# inductor_test.net
KiCad netlist of a schematic drawn in EAGLE
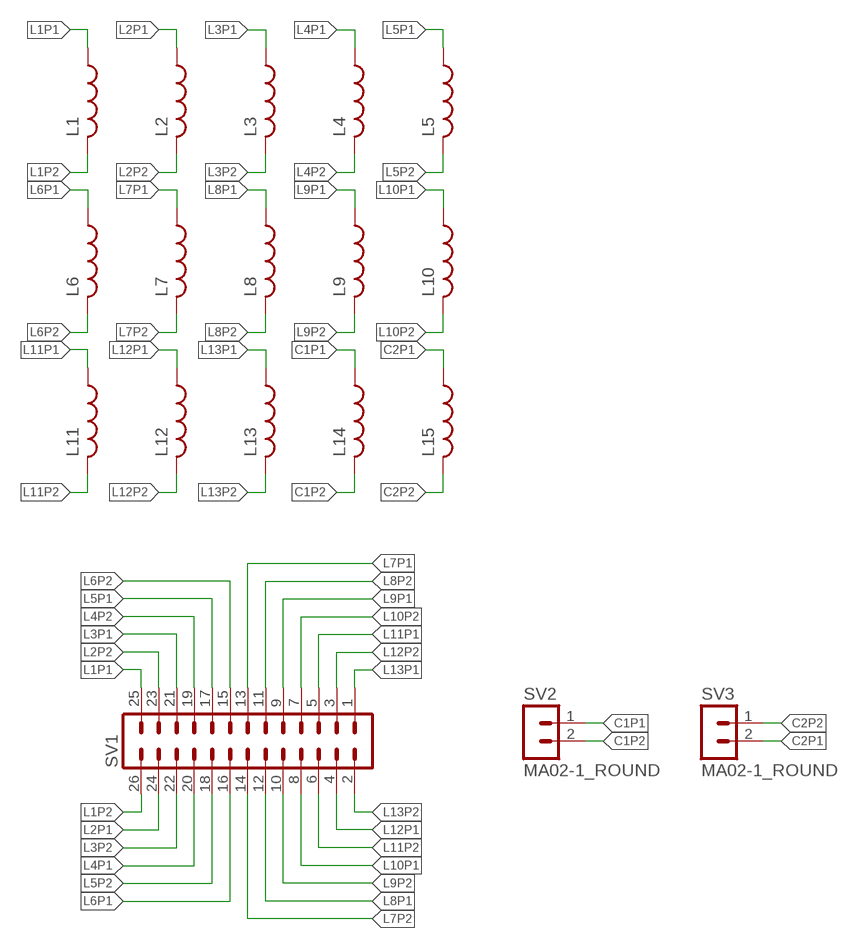
[diagram p0: schematic, sheet 1]
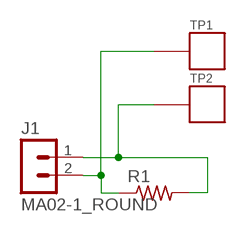
[diagram p1: schematic, sheet 2]

(export (version "E")
  (design (tool "Eeschema 10.0.6"))
  (components
    (comp (ref "L1")
      (value "L-USL0805")
      (footprint "eagle-import:L0805")
      (libsource (lib "eagle-import") (part "L-USL0805"))
    )
    (comp (ref "L2")
      (value "L-USL0805")
      (footprint "eagle-import:L0805")
      (libsource (lib "eagle-import") (part "L-USL0805"))
    )
    (comp (ref "L3")
      (value "L-USL0805")
      (footprint "eagle-import:L0805")
      (libsource (lib "eagle-import") (part "L-USL0805"))
    )
    (comp (ref "L4")
      (value "L-USL0805")
      (footprint "eagle-import:L0805")
      (libsource (lib "eagle-import") (part "L-USL0805"))
    )
    (comp (ref "L5")
      (value "L-USL0805")
      (footprint "eagle-import:L0805")
      (libsource (lib "eagle-import") (part "L-USL0805"))
    )
    (comp (ref "L6")
      (value "L-USL0805")
      (footprint "eagle-import:L0805")
      (libsource (lib "eagle-import") (part "L-USL0805"))
    )
    (comp (ref "L7")
      (value "L-USL0805")
      (footprint "eagle-import:L0805")
      (libsource (lib "eagle-import") (part "L-USL0805"))
    )
    (comp (ref "L8")
      (value "L-USL0805")
      (footprint "eagle-import:L0805")
      (libsource (lib "eagle-import") (part "L-USL0805"))
    )
    (comp (ref "L9")
      (value "L-USL0805")
      (footprint "eagle-import:L0805")
      (libsource (lib "eagle-import") (part "L-USL0805"))
    )
    (comp (ref "L10")
      (value "L-USL0805")
      (footprint "eagle-import:L0805")
      (libsource (lib "eagle-import") (part "L-USL0805"))
    )
    (comp (ref "L11")
      (value "L-USL0805")
      (footprint "eagle-import:L0805")
      (libsource (lib "eagle-import") (part "L-USL0805"))
    )
    (comp (ref "L12")
      (value "L-USL0805")
      (footprint "eagle-import:L0805")
      (libsource (lib "eagle-import") (part "L-USL0805"))
    )
    (comp (ref "L13")
      (value "L-USL0805")
      (footprint "eagle-import:L0805")
      (libsource (lib "eagle-import") (part "L-USL0805"))
    )
    (comp (ref "L14")
      (value "L-USL0805")
      (footprint "eagle-import:L0805")
      (libsource (lib "eagle-import") (part "L-USL0805"))
    )
    (comp (ref "L15")
      (value "L-USL0805")
      (footprint "eagle-import:L0805")
      (libsource (lib "eagle-import") (part "L-USL0805"))
    )
    (comp (ref "SV1")
      (value "MA13-2BARE")
      (footprint "eagle-import:MA13-2_BARE")
      (libsource (lib "eagle-import") (part "MA13-2BARE"))
    )
    (comp (ref "SV2")
      (value "MA02-1_ROUND")
      (footprint "eagle-import:MA02-1_ROUND")
      (libsource (lib "eagle-import") (part "MA02-1_ROUND"))
    )
    (comp (ref "SV3")
      (value "MA02-1_ROUND")
      (footprint "eagle-import:MA02-1_ROUND")
      (libsource (lib "eagle-import") (part "MA02-1_ROUND"))
    )
    (comp (ref "J1")
      (value "MA02-1_ROUND")
      (footprint "eagle-import:MA02-1_ROUND")
      (libsource (lib "eagle-import") (part "MA02-1_ROUND"))
    )
    (comp (ref "R1")
      (value "R-US_R0603")
      (footprint "eagle-import:R0603")
      (libsource (lib "eagle-import") (part "R-US_R0603"))
    )
    (comp (ref "TP1")
      (value "TP_STD")
      (footprint "eagle-import:TP")
      (libsource (lib "eagle-import") (part "TP_STD"))
    )
    (comp (ref "TP2")
      (value "TP_STD")
      (footprint "eagle-import:TP")
      (libsource (lib "eagle-import") (part "TP_STD"))
    )
  )
  (nets
    (net (code "1") (name "C1P1") (class "Default")
      (node (ref "L14") (pin "1") (pinfunction "1_1") (pintype "passive"))
      (node (ref "SV2") (pin "1") (pinfunction "1_1") (pintype "passive"))
    )
    (net (code "2") (name "C1P2") (class "Default")
      (node (ref "L14") (pin "2") (pinfunction "2_2") (pintype "passive"))
      (node (ref "SV2") (pin "2") (pinfunction "2_2") (pintype "passive"))
    )
    (net (code "3") (name "C2P1") (class "Default")
      (node (ref "L15") (pin "1") (pinfunction "1_1") (pintype "passive"))
      (node (ref "SV3") (pin "2") (pinfunction "2_2") (pintype "passive"))
    )
    (net (code "4") (name "C2P2") (class "Default")
      (node (ref "L15") (pin "2") (pinfunction "2_2") (pintype "passive"))
      (node (ref "SV3") (pin "1") (pinfunction "1_1") (pintype "passive"))
    )
    (net (code "5") (name "L1P1") (class "Default")
      (node (ref "L1") (pin "1") (pinfunction "1_1") (pintype "passive"))
      (node (ref "SV1") (pin "25") (pinfunction "25_25") (pintype "passive"))
    )
    (net (code "6") (name "L1P2") (class "Default")
      (node (ref "L1") (pin "2") (pinfunction "2_2") (pintype "passive"))
      (node (ref "SV1") (pin "26") (pinfunction "26_26") (pintype "passive"))
    )
    (net (code "7") (name "L2P1") (class "Default")
      (node (ref "L2") (pin "1") (pinfunction "1_1") (pintype "passive"))
      (node (ref "SV1") (pin "24") (pinfunction "24_24") (pintype "passive"))
    )
    (net (code "8") (name "L2P2") (class "Default")
      (node (ref "L2") (pin "2") (pinfunction "2_2") (pintype "passive"))
      (node (ref "SV1") (pin "23") (pinfunction "23_23") (pintype "passive"))
    )
    (net (code "9") (name "L3P1") (class "Default")
      (node (ref "L3") (pin "1") (pinfunction "1_1") (pintype "passive"))
      (node (ref "SV1") (pin "21") (pinfunction "21_21") (pintype "passive"))
    )
    (net (code "10") (name "L3P2") (class "Default")
      (node (ref "L3") (pin "2") (pinfunction "2_2") (pintype "passive"))
      (node (ref "SV1") (pin "22") (pinfunction "22_22") (pintype "passive"))
    )
    (net (code "11") (name "L4P1") (class "Default")
      (node (ref "L4") (pin "1") (pinfunction "1_1") (pintype "passive"))
      (node (ref "SV1") (pin "20") (pinfunction "20_20") (pintype "passive"))
    )
    (net (code "12") (name "L4P2") (class "Default")
      (node (ref "L4") (pin "2") (pinfunction "2_2") (pintype "passive"))
      (node (ref "SV1") (pin "19") (pinfunction "19_19") (pintype "passive"))
    )
    (net (code "13") (name "L5P1") (class "Default")
      (node (ref "L5") (pin "1") (pinfunction "1_1") (pintype "passive"))
      (node (ref "SV1") (pin "17") (pinfunction "17_17") (pintype "passive"))
    )
    (net (code "14") (name "L5P2") (class "Default")
      (node (ref "L5") (pin "2") (pinfunction "2_2") (pintype "passive"))
      (node (ref "SV1") (pin "18") (pinfunction "18_18") (pintype "passive"))
    )
    (net (code "15") (name "L6P1") (class "Default")
      (node (ref "L6") (pin "1") (pinfunction "1_1") (pintype "passive"))
      (node (ref "SV1") (pin "16") (pinfunction "16_16") (pintype "passive"))
    )
    (net (code "16") (name "L6P2") (class "Default")
      (node (ref "L6") (pin "2") (pinfunction "2_2") (pintype "passive"))
      (node (ref "SV1") (pin "15") (pinfunction "15_15") (pintype "passive"))
    )
    (net (code "17") (name "L7P1") (class "Default")
      (node (ref "L7") (pin "1") (pinfunction "1_1") (pintype "passive"))
      (node (ref "SV1") (pin "13") (pinfunction "13_13") (pintype "passive"))
    )
    (net (code "18") (name "L7P2") (class "Default")
      (node (ref "L7") (pin "2") (pinfunction "2_2") (pintype "passive"))
      (node (ref "SV1") (pin "14") (pinfunction "14_14") (pintype "passive"))
    )
    (net (code "19") (name "L8P1") (class "Default")
      (node (ref "L8") (pin "1") (pinfunction "1_1") (pintype "passive"))
      (node (ref "SV1") (pin "12") (pinfunction "12_12") (pintype "passive"))
    )
    (net (code "20") (name "L8P2") (class "Default")
      (node (ref "L8") (pin "2") (pinfunction "2_2") (pintype "passive"))
      (node (ref "SV1") (pin "11") (pinfunction "11_11") (pintype "passive"))
    )
    (net (code "21") (name "L9P1") (class "Default")
      (node (ref "L9") (pin "1") (pinfunction "1_1") (pintype "passive"))
      (node (ref "SV1") (pin "9") (pinfunction "9_9") (pintype "passive"))
    )
    (net (code "22") (name "L9P2") (class "Default")
      (node (ref "L9") (pin "2") (pinfunction "2_2") (pintype "passive"))
      (node (ref "SV1") (pin "10") (pinfunction "10_10") (pintype "passive"))
    )
    (net (code "23") (name "L10P1") (class "Default")
      (node (ref "L10") (pin "1") (pinfunction "1_1") (pintype "passive"))
      (node (ref "SV1") (pin "8") (pinfunction "8_8") (pintype "passive"))
    )
    (net (code "24") (name "L10P2") (class "Default")
      (node (ref "L10") (pin "2") (pinfunction "2_2") (pintype "passive"))
      (node (ref "SV1") (pin "7") (pinfunction "7_7") (pintype "passive"))
    )
    (net (code "25") (name "L11P1") (class "Default")
      (node (ref "L11") (pin "1") (pinfunction "1_1") (pintype "passive"))
      (node (ref "SV1") (pin "5") (pinfunction "5_5") (pintype "passive"))
    )
    (net (code "26") (name "L11P2") (class "Default")
      (node (ref "L11") (pin "2") (pinfunction "2_2") (pintype "passive"))
      (node (ref "SV1") (pin "6") (pinfunction "6_6") (pintype "passive"))
    )
    (net (code "27") (name "L12P1") (class "Default")
      (node (ref "L12") (pin "1") (pinfunction "1_1") (pintype "passive"))
      (node (ref "SV1") (pin "4") (pinfunction "4_4") (pintype "passive"))
    )
    (net (code "28") (name "L12P2") (class "Default")
      (node (ref "L12") (pin "2") (pinfunction "2_2") (pintype "passive"))
      (node (ref "SV1") (pin "3") (pinfunction "3_3") (pintype "passive"))
    )
    (net (code "29") (name "L13P1") (class "Default")
      (node (ref "L13") (pin "1") (pinfunction "1_1") (pintype "passive"))
      (node (ref "SV1") (pin "1") (pinfunction "1_1") (pintype "passive"))
    )
    (net (code "30") (name "L13P2") (class "Default")
      (node (ref "L13") (pin "2") (pinfunction "2_2") (pintype "passive"))
      (node (ref "SV1") (pin "2") (pinfunction "2_2") (pintype "passive"))
    )
    (net (code "31") (name "Net-(J1-Pad1)") (class "Default")
      (node (ref "J1") (pin "1") (pinfunction "1_1") (pintype "passive"))
      (node (ref "R1") (pin "2") (pinfunction "2_2") (pintype "passive"))
      (node (ref "TP2") (pin "P$1") (pinfunction "P$1_P$1") (pintype "bidirectional"))
    )
    (net (code "32") (name "Net-(J1-Pad2)") (class "Default")
      (node (ref "J1") (pin "2") (pinfunction "2_2") (pintype "passive"))
      (node (ref "R1") (pin "1") (pinfunction "1_1") (pintype "passive"))
      (node (ref "TP1") (pin "P$1") (pinfunction "P$1_P$1") (pintype "bidirectional"))
    )
  )
)
